# PWM_Isolator.net
KiCad netlist of a schematic drawn in Altium Designer
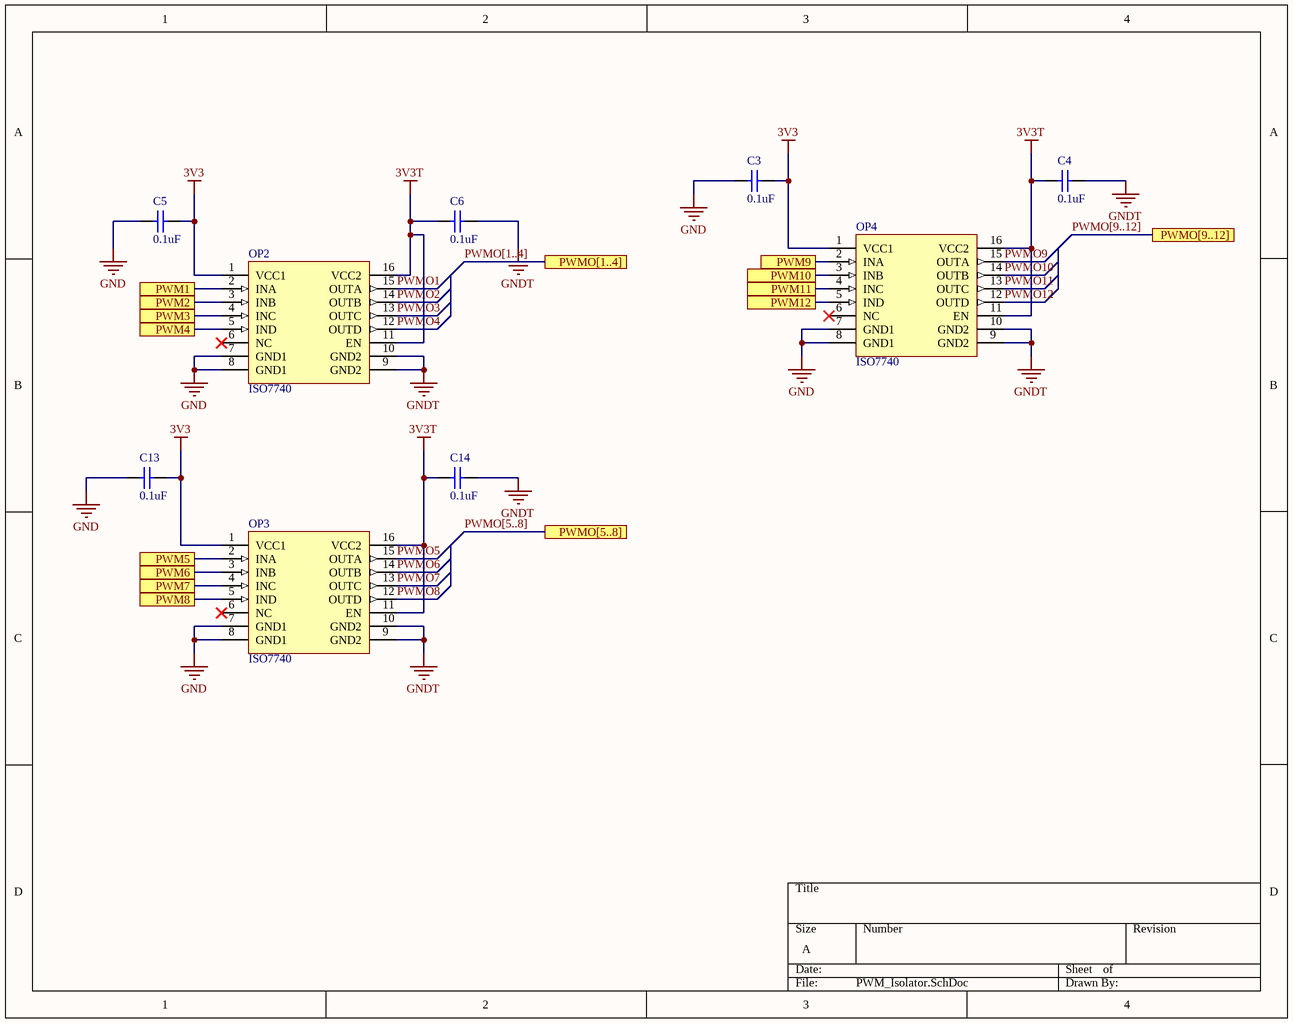
[diagram p0: PWM_Isolator.SchDoc]

(export (version "E")
  (design (tool "Eeschema 10.0.6"))
  (components
    (comp (ref "C3")
      (value "0.1uF")
      (footprint "CAPC1608X97X38NL12T08")
      (description "CAP CER 0.1UF 25V X7R 0603")
      (fields (field (name "MANUFACTURER") "Vitramon") (field (name "PART NUMBER") "VJ0603Y-104KXXAC"))
      (libsource (lib "Main") (part "VJ0603Y104KXXAC"))
    )
    (comp (ref "C4")
      (value "0.1uF")
      (footprint "CAPC1608X97X38NL12T08")
      (description "CAP CER 0.1UF 25V X7R 0603")
      (fields (field (name "MANUFACTURER") "Vitramon") (field (name "PART NUMBER") "VJ0603Y-104KXXAC"))
      (libsource (lib "Main") (part "VJ0603Y104KXXAC"))
    )
    (comp (ref "C5")
      (value "0.1uF")
      (footprint "CAPC1608X97X38NL12T08")
      (description "CAP CER 0.1UF 25V X7R 0603")
      (fields (field (name "MANUFACTURER") "Vitramon") (field (name "PART NUMBER") "VJ0603Y-104KXXAC"))
      (libsource (lib "Main") (part "VJ0603Y104KXXAC"))
    )
    (comp (ref "C6")
      (value "0.1uF")
      (footprint "CAPC1608X97X38NL12T08")
      (description "CAP CER 0.1UF 25V X7R 0603")
      (fields (field (name "MANUFACTURER") "Vitramon") (field (name "PART NUMBER") "VJ0603Y-104KXXAC"))
      (libsource (lib "Main") (part "VJ0603Y104KXXAC"))
    )
    (comp (ref "C13")
      (value "0.1uF")
      (footprint "CAPC1608X97X38NL12T08")
      (description "CAP CER 0.1UF 25V X7R 0603")
      (fields (field (name "MANUFACTURER") "Vitramon") (field (name "PART NUMBER") "VJ0603Y-104KXXAC"))
      (libsource (lib "Main") (part "VJ0603Y104KXXAC"))
    )
    (comp (ref "C14")
      (value "0.1uF")
      (footprint "CAPC1608X97X38NL12T08")
      (description "CAP CER 0.1UF 25V X7R 0603")
      (fields (field (name "MANUFACTURER") "Vitramon") (field (name "PART NUMBER") "VJ0603Y-104KXXAC"))
      (libsource (lib "Main") (part "VJ0603Y104KXXAC"))
    )
    (comp (ref "OP2")
      (value "ISO7740")
      (footprint "DBQ0016A_M")
      (libsource (lib "Main") (part "ISO7740DBQR"))
    )
    (comp (ref "OP3")
      (value "ISO7740")
      (footprint "DBQ0016A_M")
      (libsource (lib "Main") (part "ISO7740DBQR"))
    )
    (comp (ref "OP4")
      (value "ISO7740")
      (footprint "DBQ0016A_M")
      (libsource (lib "Main") (part "ISO7740DBQR"))
    )
  )
  (nets
    (net (code "1") (name "/PWM1") (class "Default")
      (node (ref "OP2") (pin "2") (pinfunction "INA_2") (pintype "input"))
    )
    (net (code "2") (name "/PWM2") (class "Default")
      (node (ref "OP2") (pin "3") (pinfunction "INB_3") (pintype "input"))
    )
    (net (code "3") (name "/PWM3") (class "Default")
      (node (ref "OP2") (pin "4") (pinfunction "INC_4") (pintype "input"))
    )
    (net (code "4") (name "/PWM4") (class "Default")
      (node (ref "OP2") (pin "5") (pinfunction "IND_5") (pintype "input"))
    )
    (net (code "5") (name "/PWM5") (class "Default")
      (node (ref "OP3") (pin "2") (pinfunction "INA_2") (pintype "input"))
    )
    (net (code "6") (name "/PWM6") (class "Default")
      (node (ref "OP3") (pin "3") (pinfunction "INB_3") (pintype "input"))
    )
    (net (code "7") (name "/PWM7") (class "Default")
      (node (ref "OP3") (pin "4") (pinfunction "INC_4") (pintype "input"))
    )
    (net (code "8") (name "/PWM8") (class "Default")
      (node (ref "OP3") (pin "5") (pinfunction "IND_5") (pintype "input"))
    )
    (net (code "9") (name "/PWM9") (class "Default")
      (node (ref "OP4") (pin "2") (pinfunction "INA_2") (pintype "input"))
    )
    (net (code "10") (name "/PWM10") (class "Default")
      (node (ref "OP4") (pin "3") (pinfunction "INB_3") (pintype "input"))
    )
    (net (code "11") (name "/PWM11") (class "Default")
      (node (ref "OP4") (pin "4") (pinfunction "INC_4") (pintype "input"))
    )
    (net (code "12") (name "/PWM12") (class "Default")
      (node (ref "OP4") (pin "5") (pinfunction "IND_5") (pintype "input"))
    )
    (net (code "13") (name "/PWMO1") (class "Default")
      (node (ref "OP2") (pin "15") (pinfunction "OUTA_15") (pintype "output"))
    )
    (net (code "14") (name "/PWMO2") (class "Default")
      (node (ref "OP2") (pin "14") (pinfunction "OUTB_14") (pintype "output"))
    )
    (net (code "15") (name "/PWMO3") (class "Default")
      (node (ref "OP2") (pin "13") (pinfunction "OUTC_13") (pintype "output"))
    )
    (net (code "16") (name "/PWMO4") (class "Default")
      (node (ref "OP2") (pin "12") (pinfunction "OUTD_12") (pintype "output"))
    )
    (net (code "17") (name "/PWMO5") (class "Default")
      (node (ref "OP3") (pin "15") (pinfunction "OUTA_15") (pintype "output"))
    )
    (net (code "18") (name "/PWMO6") (class "Default")
      (node (ref "OP3") (pin "14") (pinfunction "OUTB_14") (pintype "output"))
    )
    (net (code "19") (name "/PWMO7") (class "Default")
      (node (ref "OP3") (pin "13") (pinfunction "OUTC_13") (pintype "output"))
    )
    (net (code "20") (name "/PWMO8") (class "Default")
      (node (ref "OP3") (pin "12") (pinfunction "OUTD_12") (pintype "output"))
    )
    (net (code "21") (name "/PWMO9") (class "Default")
      (node (ref "OP4") (pin "15") (pinfunction "OUTA_15") (pintype "output"))
    )
    (net (code "22") (name "/PWMO10") (class "Default")
      (node (ref "OP4") (pin "14") (pinfunction "OUTB_14") (pintype "output"))
    )
    (net (code "23") (name "/PWMO11") (class "Default")
      (node (ref "OP4") (pin "13") (pinfunction "OUTC_13") (pintype "output"))
    )
    (net (code "24") (name "/PWMO12") (class "Default")
      (node (ref "OP4") (pin "12") (pinfunction "OUTD_12") (pintype "output"))
    )
    (net (code "28") (name "3V3") (class "Default")
      (node (ref "C13") (pin "2") (pinfunction "2_2") (pintype "passive"))
      (node (ref "C3") (pin "2") (pinfunction "2_2") (pintype "passive"))
      (node (ref "C5") (pin "2") (pinfunction "2_2") (pintype "passive"))
      (node (ref "OP2") (pin "1") (pinfunction "VCC1_1") (pintype "power_in"))
      (node (ref "OP3") (pin "1") (pinfunction "VCC1_1") (pintype "power_in"))
      (node (ref "OP4") (pin "1") (pinfunction "VCC1_1") (pintype "power_in"))
    )
    (net (code "29") (name "3V3T") (class "Default")
      (node (ref "C14") (pin "1") (pinfunction "1_1") (pintype "passive"))
      (node (ref "C4") (pin "1") (pinfunction "1_1") (pintype "passive"))
      (node (ref "C6") (pin "1") (pinfunction "1_1") (pintype "passive"))
      (node (ref "OP2") (pin "11") (pinfunction "EN_11") (pintype "passive"))
      (node (ref "OP2") (pin "16") (pinfunction "VCC2_16") (pintype "power_in"))
      (node (ref "OP3") (pin "11") (pinfunction "EN_11") (pintype "passive"))
      (node (ref "OP3") (pin "16") (pinfunction "VCC2_16") (pintype "power_in"))
      (node (ref "OP4") (pin "11") (pinfunction "EN_11") (pintype "passive"))
      (node (ref "OP4") (pin "16") (pinfunction "VCC2_16") (pintype "power_in"))
    )
    (net (code "30") (name "GND") (class "Default")
      (node (ref "C13") (pin "1") (pinfunction "1_1") (pintype "passive"))
      (node (ref "C3") (pin "1") (pinfunction "1_1") (pintype "passive"))
      (node (ref "C5") (pin "1") (pinfunction "1_1") (pintype "passive"))
      (node (ref "OP2") (pin "7") (pinfunction "GND1_7") (pintype "passive"))
      (node (ref "OP2") (pin "8") (pinfunction "GND1_8") (pintype "passive"))
      (node (ref "OP3") (pin "7") (pinfunction "GND1_7") (pintype "passive"))
      (node (ref "OP3") (pin "8") (pinfunction "GND1_8") (pintype "passive"))
      (node (ref "OP4") (pin "7") (pinfunction "GND1_7") (pintype "passive"))
      (node (ref "OP4") (pin "8") (pinfunction "GND1_8") (pintype "passive"))
    )
    (net (code "31") (name "GNDT") (class "Default")
      (node (ref "C14") (pin "2") (pinfunction "2_2") (pintype "passive"))
      (node (ref "C4") (pin "2") (pinfunction "2_2") (pintype "passive"))
      (node (ref "C6") (pin "2") (pinfunction "2_2") (pintype "passive"))
      (node (ref "OP2") (pin "10") (pinfunction "GND2_10") (pintype "passive"))
      (node (ref "OP2") (pin "9") (pinfunction "GND2_9") (pintype "passive"))
      (node (ref "OP3") (pin "10") (pinfunction "GND2_10") (pintype "passive"))
      (node (ref "OP3") (pin "9") (pinfunction "GND2_9") (pintype "passive"))
      (node (ref "OP4") (pin "10") (pinfunction "GND2_10") (pintype "passive"))
      (node (ref "OP4") (pin "9") (pinfunction "GND2_9") (pintype "passive"))
    )
    (net (code "32") (name "unconnected-(OP2-NC-Pad6)") (class "Default")
      (node (ref "OP2") (pin "6") (pinfunction "NC_6") (pintype "passive+no_connect"))
    )
    (net (code "33") (name "unconnected-(OP3-NC-Pad6)") (class "Default")
      (node (ref "OP3") (pin "6") (pinfunction "NC_6") (pintype "passive+no_connect"))
    )
    (net (code "34") (name "unconnected-(OP4-NC-Pad6)") (class "Default")
      (node (ref "OP4") (pin "6") (pinfunction "NC_6") (pintype "passive+no_connect"))
    )
  )
)
